# P_ytka.net
KiCad netlist of a schematic drawn in EAGLE
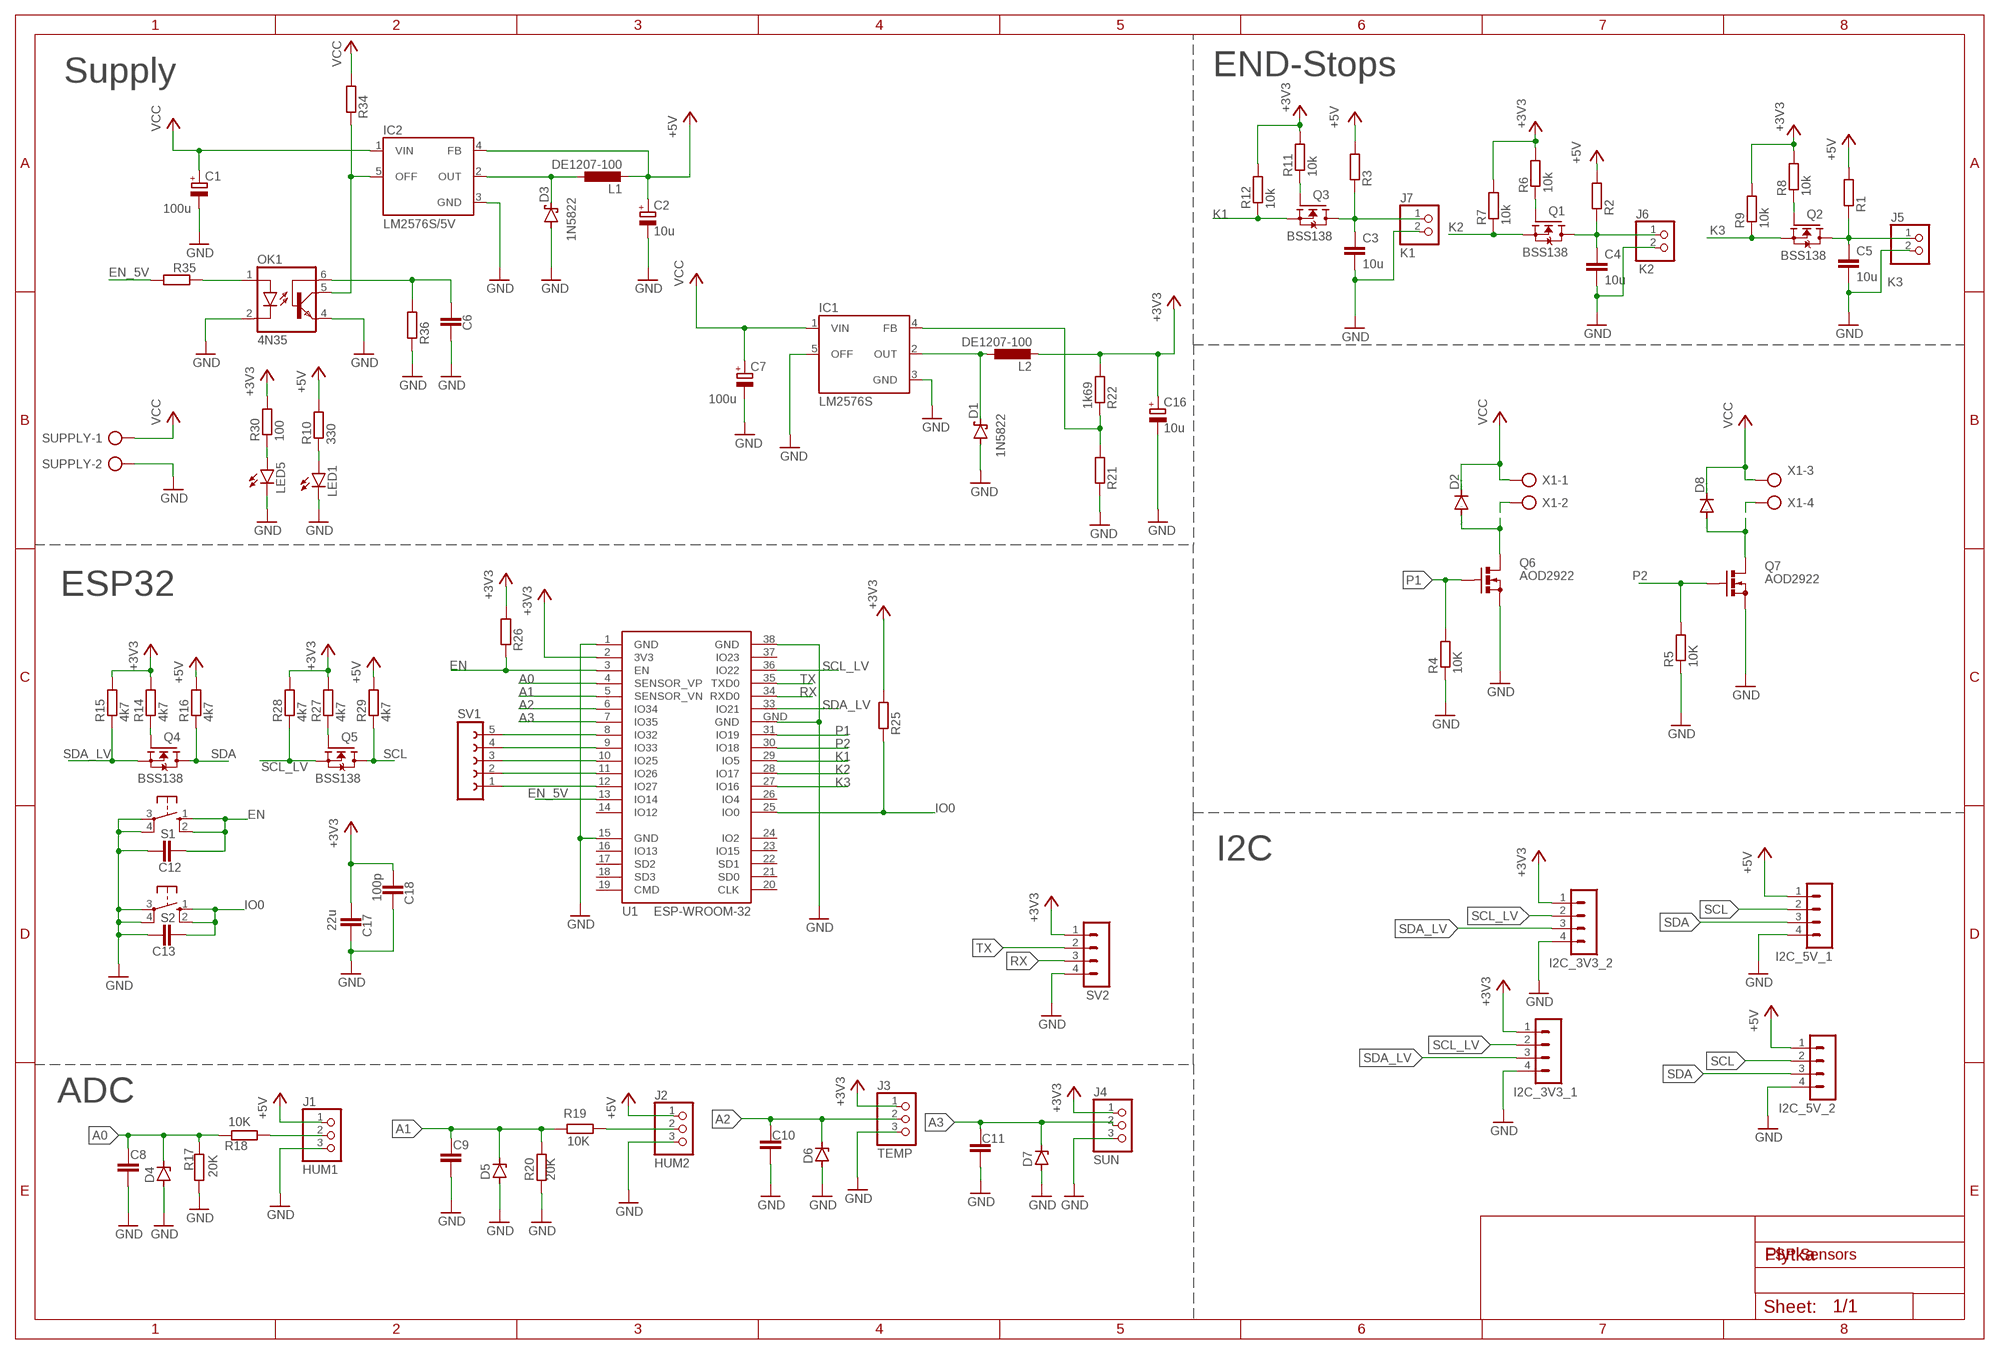
[diagram p0: schematic, sheet 1]

(export (version "E")
  (design (tool "Eeschema 10.0.6"))
  (components
    (comp (ref "C1")
      (value "100u")
      (footprint "eagle-import:E2,5-6")
      (libsource (lib "eagle-import") (part "CPOL-EUE2.5-6"))
    )
    (comp (ref "C2")
      (value "10u")
      (footprint "eagle-import:E3,5-8")
      (libsource (lib "eagle-import") (part "CPOL-EUE3.5-8"))
    )
    (comp (ref "C3")
      (value "10u")
      (footprint "eagle-import:C0805K")
      (libsource (lib "eagle-import") (part "C-EUC0805K"))
    )
    (comp (ref "C4")
      (value "10u")
      (footprint "eagle-import:C0805K")
      (libsource (lib "eagle-import") (part "C-EUC0805K"))
    )
    (comp (ref "C5")
      (value "10u")
      (footprint "eagle-import:C0805K")
      (libsource (lib "eagle-import") (part "C-EUC0805K"))
    )
    (comp (ref "C6")
      (value "C-EUC0805K")
      (footprint "eagle-import:C0805K")
      (libsource (lib "eagle-import") (part "C-EUC0805K"))
    )
    (comp (ref "C7")
      (value "100u")
      (footprint "eagle-import:E2,5-6")
      (libsource (lib "eagle-import") (part "CPOL-EUE2.5-6"))
    )
    (comp (ref "C8")
      (value "C-EUC0805K")
      (footprint "eagle-import:C0805K")
      (libsource (lib "eagle-import") (part "C-EUC0805K"))
    )
    (comp (ref "C9")
      (value "C-EUC0805K")
      (footprint "eagle-import:C0805K")
      (libsource (lib "eagle-import") (part "C-EUC0805K"))
    )
    (comp (ref "C10")
      (value "C-EUC0805K")
      (footprint "eagle-import:C0805K")
      (libsource (lib "eagle-import") (part "C-EUC0805K"))
    )
    (comp (ref "C11")
      (value "C-EUC0805K")
      (footprint "eagle-import:C0805K")
      (libsource (lib "eagle-import") (part "C-EUC0805K"))
    )
    (comp (ref "C12")
      (value "C-EUC0805K")
      (footprint "eagle-import:C0805K")
      (libsource (lib "eagle-import") (part "C-EUC0805K"))
    )
    (comp (ref "C13")
      (value "C-EUC0805K")
      (footprint "eagle-import:C0805K")
      (libsource (lib "eagle-import") (part "C-EUC0805K"))
    )
    (comp (ref "C16")
      (value "10u")
      (footprint "eagle-import:E3,5-8")
      (libsource (lib "eagle-import") (part "CPOL-EUE3.5-8"))
    )
    (comp (ref "C17")
      (value "22u")
      (footprint "eagle-import:C0805K")
      (libsource (lib "eagle-import") (part "C-EUC0805K"))
    )
    (comp (ref "C18")
      (value "100p")
      (footprint "eagle-import:C0805K")
      (libsource (lib "eagle-import") (part "C-EUC0805K"))
    )
    (comp (ref "D1")
      (value "1N5822")
      (footprint "eagle-import:C4111-15")
      (libsource (lib "eagle-import") (part "1N5908"))
    )
    (comp (ref "D2")
      (value "DIODE-DO214AC")
      (footprint "eagle-import:DO214AC")
      (libsource (lib "eagle-import") (part "DIODE-DO214AC"))
    )
    (comp (ref "D3")
      (value "1N5822")
      (footprint "eagle-import:C4111-15")
      (libsource (lib "eagle-import") (part "1N5908"))
    )
    (comp (ref "D4")
      (value "ZENER-DIODESOD80C")
      (footprint "eagle-import:SOD80C")
      (libsource (lib "eagle-import") (part "ZENER-DIODESOD80C"))
    )
    (comp (ref "D5")
      (value "ZENER-DIODESOD80C")
      (footprint "eagle-import:SOD80C")
      (libsource (lib "eagle-import") (part "ZENER-DIODESOD80C"))
    )
    (comp (ref "D6")
      (value "ZENER-DIODESOD80C")
      (footprint "eagle-import:SOD80C")
      (libsource (lib "eagle-import") (part "ZENER-DIODESOD80C"))
    )
    (comp (ref "D7")
      (value "ZENER-DIODESOD80C")
      (footprint "eagle-import:SOD80C")
      (libsource (lib "eagle-import") (part "ZENER-DIODESOD80C"))
    )
    (comp (ref "D8")
      (value "DIODE-DO214AC")
      (footprint "eagle-import:DO214AC")
      (libsource (lib "eagle-import") (part "DIODE-DO214AC"))
    )
    (comp (ref "I2C_3V3_1")
      (value "MA04-1")
      (footprint "eagle-import:MA04-1")
      (libsource (lib "eagle-import") (part "MA04-1"))
    )
    (comp (ref "I2C_3V3_2")
      (value "MA04-1")
      (footprint "eagle-import:MA04-1")
      (libsource (lib "eagle-import") (part "MA04-1"))
    )
    (comp (ref "I2C_5V_1")
      (value "MA04-1")
      (footprint "eagle-import:MA04-1")
      (libsource (lib "eagle-import") (part "MA04-1"))
    )
    (comp (ref "I2C_5V_2")
      (value "MA04-1")
      (footprint "eagle-import:MA04-1")
      (libsource (lib "eagle-import") (part "MA04-1"))
    )
    (comp (ref "IC1")
      (value "LM2576S")
      (footprint "eagle-import:TO263-5")
      (libsource (lib "eagle-import") (part "LM2576S"))
    )
    (comp (ref "IC2")
      (value "LM2576S/5V")
      (footprint "eagle-import:TO220-5")
      (libsource (lib "eagle-import") (part "LM2576T"))
    )
    (comp (ref "J1")
      (value "HUM1")
      (footprint "eagle-import:W_TYPE_2MM_3_N")
      (libsource (lib "eagle-import") (part "WT-2MM-3PINSTRAIGHT"))
    )
    (comp (ref "J2")
      (value "HUM2")
      (footprint "eagle-import:W_TYPE_2MM_3_N")
      (libsource (lib "eagle-import") (part "WT-2MM-3PINSTRAIGHT"))
    )
    (comp (ref "J3")
      (value "TEMP")
      (footprint "eagle-import:W_TYPE_2MM_3_N")
      (libsource (lib "eagle-import") (part "WT-2MM-3PINSTRAIGHT"))
    )
    (comp (ref "J4")
      (value "SUN")
      (footprint "eagle-import:W_TYPE_2MM_3_N")
      (libsource (lib "eagle-import") (part "WT-2MM-3PINSTRAIGHT"))
    )
    (comp (ref "J5")
      (value "K3")
      (footprint "eagle-import:W_TYPE_2MM_2_N")
      (libsource (lib "eagle-import") (part "WT-2MM-2PINSTRAIGHT"))
    )
    (comp (ref "J6")
      (value "K2")
      (footprint "eagle-import:W_TYPE_2MM_2_N")
      (libsource (lib "eagle-import") (part "WT-2MM-2PINSTRAIGHT"))
    )
    (comp (ref "J7")
      (value "K1")
      (footprint "eagle-import:W_TYPE_2MM_2_N")
      (libsource (lib "eagle-import") (part "WT-2MM-2PINSTRAIGHT"))
    )
    (comp (ref "L1")
      (value "DE1207-100")
      (footprint "eagle-import:DE1207")
      (libsource (lib "eagle-import") (part "DE1207-100"))
    )
    (comp (ref "L2")
      (value "DE1207-100")
      (footprint "eagle-import:DE1207")
      (libsource (lib "eagle-import") (part "DE1207-100"))
    )
    (comp (ref "LED1")
      (value "LEDSML0805")
      (footprint "eagle-import:SML0805")
      (libsource (lib "eagle-import") (part "LEDSML0805"))
    )
    (comp (ref "LED5")
      (value "LEDSML0805")
      (footprint "eagle-import:SML0805")
      (libsource (lib "eagle-import") (part "LEDSML0805"))
    )
    (comp (ref "OK1")
      (value "4N35")
      (footprint "eagle-import:DIL06")
      (fields (field (name "MF") "FAIRCHILD SEMICONDUCTOR"))
      (libsource (lib "eagle-import") (part "4N35"))
    )
    (comp (ref "Q1")
      (value "BSS138")
      (footprint "eagle-import:SOT23")
      (fields (field (name "MF") "Fairchild"))
      (libsource (lib "eagle-import") (part "BSS138"))
    )
    (comp (ref "Q2")
      (value "BSS138")
      (footprint "eagle-import:SOT23")
      (fields (field (name "MF") "Fairchild"))
      (libsource (lib "eagle-import") (part "BSS138"))
    )
    (comp (ref "Q3")
      (value "BSS138")
      (footprint "eagle-import:SOT23")
      (fields (field (name "MF") "Fairchild"))
      (libsource (lib "eagle-import") (part "BSS138"))
    )
    (comp (ref "Q4")
      (value "BSS138")
      (footprint "eagle-import:SOT23")
      (fields (field (name "MF") "Fairchild"))
      (libsource (lib "eagle-import") (part "BSS138"))
    )
    (comp (ref "Q5")
      (value "BSS138")
      (footprint "eagle-import:SOT23")
      (fields (field (name "MF") "Fairchild"))
      (libsource (lib "eagle-import") (part "BSS138"))
    )
    (comp (ref "Q6")
      (value "AOD2922")
      (footprint "eagle-import:TO252AA")
      (libsource (lib "eagle-import") (part "MOSFET_NIXTY8N65X2"))
    )
    (comp (ref "Q7")
      (value "AOD2922")
      (footprint "eagle-import:TO252AA")
      (libsource (lib "eagle-import") (part "MOSFET_NIXTY8N65X2"))
    )
    (comp (ref "R1")
      (value "R-EU_R0805")
      (footprint "eagle-import:R0805")
      (libsource (lib "eagle-import") (part "R-EU_R0805"))
    )
    (comp (ref "R2")
      (value "R-EU_R0805")
      (footprint "eagle-import:R0805")
      (libsource (lib "eagle-import") (part "R-EU_R0805"))
    )
    (comp (ref "R3")
      (value "R-EU_R0805")
      (footprint "eagle-import:R0805")
      (libsource (lib "eagle-import") (part "R-EU_R0805"))
    )
    (comp (ref "R4")
      (value "10K")
      (footprint "eagle-import:R0805")
      (libsource (lib "eagle-import") (part "R-EU_R0805"))
    )
    (comp (ref "R5")
      (value "10K")
      (footprint "eagle-import:R0805")
      (libsource (lib "eagle-import") (part "R-EU_R0805"))
    )
    (comp (ref "R6")
      (value "10k")
      (footprint "eagle-import:R0805")
      (libsource (lib "eagle-import") (part "R-EU_R0805"))
    )
    (comp (ref "R7")
      (value "10k")
      (footprint "eagle-import:R0805")
      (libsource (lib "eagle-import") (part "R-EU_R0805"))
    )
    (comp (ref "R8")
      (value "10k")
      (footprint "eagle-import:R0805")
      (libsource (lib "eagle-import") (part "R-EU_R0805"))
    )
    (comp (ref "R9")
      (value "10k")
      (footprint "eagle-import:R0805")
      (libsource (lib "eagle-import") (part "R-EU_R0805"))
    )
    (comp (ref "R10")
      (value "330")
      (footprint "eagle-import:R0805")
      (libsource (lib "eagle-import") (part "R-EU_R0805"))
    )
    (comp (ref "R11")
      (value "10k")
      (footprint "eagle-import:R0805")
      (libsource (lib "eagle-import") (part "R-EU_R0805"))
    )
    (comp (ref "R12")
      (value "10k")
      (footprint "eagle-import:R0805")
      (libsource (lib "eagle-import") (part "R-EU_R0805"))
    )
    (comp (ref "R14")
      (value "4k7")
      (footprint "eagle-import:R0805")
      (libsource (lib "eagle-import") (part "R-EU_R0805"))
    )
    (comp (ref "R15")
      (value "4k7")
      (footprint "eagle-import:R0805")
      (libsource (lib "eagle-import") (part "R-EU_R0805"))
    )
    (comp (ref "R16")
      (value "4k7")
      (footprint "eagle-import:R0805")
      (libsource (lib "eagle-import") (part "R-EU_R0805"))
    )
    (comp (ref "R17")
      (value "20K")
      (footprint "eagle-import:R0805")
      (libsource (lib "eagle-import") (part "R-EU_R0805"))
    )
    (comp (ref "R18")
      (value "10K")
      (footprint "eagle-import:R0805")
      (libsource (lib "eagle-import") (part "R-EU_R0805"))
    )
    (comp (ref "R19")
      (value "10K")
      (footprint "eagle-import:R0805")
      (libsource (lib "eagle-import") (part "R-EU_R0805"))
    )
    (comp (ref "R20")
      (value "20K")
      (footprint "eagle-import:R0805")
      (libsource (lib "eagle-import") (part "R-EU_R0805"))
    )
    (comp (ref "R21")
      (value "R-EU_R0805")
      (footprint "eagle-import:R0805")
      (libsource (lib "eagle-import") (part "R-EU_R0805"))
    )
    (comp (ref "R22")
      (value "1k69")
      (footprint "eagle-import:R0805")
      (libsource (lib "eagle-import") (part "R-EU_R0805"))
    )
    (comp (ref "R25")
      (value "R-EU_R0805")
      (footprint "eagle-import:R0805")
      (libsource (lib "eagle-import") (part "R-EU_R0805"))
    )
    (comp (ref "R26")
      (value "R-EU_R0805")
      (footprint "eagle-import:R0805")
      (libsource (lib "eagle-import") (part "R-EU_R0805"))
    )
    (comp (ref "R27")
      (value "4k7")
      (footprint "eagle-import:R0805")
      (libsource (lib "eagle-import") (part "R-EU_R0805"))
    )
    (comp (ref "R28")
      (value "4k7")
      (footprint "eagle-import:R0805")
      (libsource (lib "eagle-import") (part "R-EU_R0805"))
    )
    (comp (ref "R29")
      (value "4k7")
      (footprint "eagle-import:R0805")
      (libsource (lib "eagle-import") (part "R-EU_R0805"))
    )
    (comp (ref "R30")
      (value "100")
      (footprint "eagle-import:R0805")
      (libsource (lib "eagle-import") (part "R-EU_R0805"))
    )
    (comp (ref "R34")
      (value "R-EU_R0805")
      (footprint "eagle-import:R0805")
      (libsource (lib "eagle-import") (part "R-EU_R0805"))
    )
    (comp (ref "R35")
      (value "R-EU_R0805")
      (footprint "eagle-import:R0805")
      (libsource (lib "eagle-import") (part "R-EU_R0805"))
    )
    (comp (ref "R36")
      (value "R-EU_R0805")
      (footprint "eagle-import:R0805")
      (libsource (lib "eagle-import") (part "R-EU_R0805"))
    )
    (comp (ref "S1")
      (value "10-XX")
      (footprint "eagle-import:B3F-10XX")
      (fields (field (name "MPN") "B3F-1000"))
      (libsource (lib "eagle-import") (part "10-XX"))
    )
    (comp (ref "S2")
      (value "10-XX")
      (footprint "eagle-import:B3F-10XX")
      (fields (field (name "MPN") "B3F-1000"))
      (libsource (lib "eagle-import") (part "10-XX"))
    )
    (comp (ref "SUPPLY")
      (value "AK500/2-H")
      (footprint "eagle-import:AK500_2-H")
      (libsource (lib "eagle-import") (part "AK500/2-H"))
    )
    (comp (ref "SV1")
      (value "FE05-1")
      (footprint "eagle-import:FE05-1")
      (libsource (lib "eagle-import") (part "FE05-1"))
    )
    (comp (ref "SV2")
      (value "MA04-1")
      (footprint "eagle-import:MA04-1")
      (libsource (lib "eagle-import") (part "MA04-1"))
    )
    (comp (ref "U1")
      (value "ESP-WROOM-32")
      (footprint "eagle-import:ESP-WROOM-32")
      (libsource (lib "eagle-import") (part "ESP-WROOM-32"))
    )
    (comp (ref "X1")
      (value "+ P2")
      (footprint "eagle-import:AK500_4")
      (libsource (lib "eagle-import") (part "AK500/4"))
    )
  )
  (nets
    (net (code "1") (name "+3V3") (class "Default")
      (node (ref "C16") (pin "+") (pinfunction "+_+") (pintype "passive"))
      (node (ref "C17") (pin "2") (pinfunction "2_2") (pintype "passive"))
      (node (ref "C18") (pin "2") (pinfunction "2_2") (pintype "passive"))
      (node (ref "I2C_3V3_1") (pin "1") (pinfunction "1_1") (pintype "passive"))
      (node (ref "I2C_3V3_2") (pin "1") (pinfunction "1_1") (pintype "passive"))
      (node (ref "J3") (pin "1") (pinfunction "1_1") (pintype "passive"))
      (node (ref "J4") (pin "1") (pinfunction "1_1") (pintype "passive"))
      (node (ref "L2") (pin "2") (pinfunction "2_2") (pintype "passive"))
      (node (ref "R11") (pin "2") (pinfunction "2_2") (pintype "passive"))
      (node (ref "R12") (pin "2") (pinfunction "2_2") (pintype "passive"))
      (node (ref "R14") (pin "2") (pinfunction "2_2") (pintype "passive"))
      (node (ref "R15") (pin "2") (pinfunction "2_2") (pintype "passive"))
      (node (ref "R22") (pin "2") (pinfunction "2_2") (pintype "passive"))
      (node (ref "R25") (pin "2") (pinfunction "2_2") (pintype "passive"))
      (node (ref "R26") (pin "2") (pinfunction "2_2") (pintype "passive"))
      (node (ref "R27") (pin "2") (pinfunction "2_2") (pintype "passive"))
      (node (ref "R28") (pin "2") (pinfunction "2_2") (pintype "passive"))
      (node (ref "R30") (pin "2") (pinfunction "2_2") (pintype "passive"))
      (node (ref "R6") (pin "2") (pinfunction "2_2") (pintype "passive"))
      (node (ref "R7") (pin "2") (pinfunction "2_2") (pintype "passive"))
      (node (ref "R8") (pin "2") (pinfunction "2_2") (pintype "passive"))
      (node (ref "R9") (pin "2") (pinfunction "2_2") (pintype "passive"))
      (node (ref "SV2") (pin "1") (pinfunction "1_1") (pintype "passive"))
      (node (ref "U1") (pin "2") (pinfunction "3V3_2") (pintype "power_in"))
    )
    (net (code "2") (name "+5V") (class "Default")
      (node (ref "C2") (pin "+") (pinfunction "+_+") (pintype "passive"))
      (node (ref "I2C_5V_1") (pin "1") (pinfunction "1_1") (pintype "passive"))
      (node (ref "I2C_5V_2") (pin "1") (pinfunction "1_1") (pintype "passive"))
      (node (ref "IC2") (pin "4") (pinfunction "FB_4") (pintype "input"))
      (node (ref "J1") (pin "1") (pinfunction "1_1") (pintype "passive"))
      (node (ref "J2") (pin "1") (pinfunction "1_1") (pintype "passive"))
      (node (ref "L1") (pin "2") (pinfunction "2_2") (pintype "passive"))
      (node (ref "R1") (pin "2") (pinfunction "2_2") (pintype "passive"))
      (node (ref "R10") (pin "2") (pinfunction "2_2") (pintype "passive"))
      (node (ref "R16") (pin "2") (pinfunction "2_2") (pintype "passive"))
      (node (ref "R2") (pin "2") (pinfunction "2_2") (pintype "passive"))
      (node (ref "R29") (pin "2") (pinfunction "2_2") (pintype "passive"))
      (node (ref "R3") (pin "2") (pinfunction "2_2") (pintype "passive"))
    )
    (net (code "3") (name "/EN") (class "Default")
      (node (ref "C12") (pin "2") (pinfunction "2_2") (pintype "passive"))
      (node (ref "R26") (pin "1") (pinfunction "1_1") (pintype "passive"))
      (node (ref "S1") (pin "1") (pinfunction "S_1") (pintype "passive"))
      (node (ref "S1") (pin "2") (pinfunction "S1_2") (pintype "passive"))
      (node (ref "U1") (pin "3") (pinfunction "EN_3") (pintype "input"))
    )
    (net (code "4") (name "/EN_5V") (class "Default")
      (node (ref "R35") (pin "2") (pinfunction "2_2") (pintype "passive"))
      (node (ref "U1") (pin "13") (pinfunction "IO14_13") (pintype "bidirectional"))
    )
    (net (code "5") (name "/IO0") (class "Default")
      (node (ref "C13") (pin "2") (pinfunction "2_2") (pintype "passive"))
      (node (ref "R25") (pin "1") (pinfunction "1_1") (pintype "passive"))
      (node (ref "S2") (pin "1") (pinfunction "S_1") (pintype "passive"))
      (node (ref "S2") (pin "2") (pinfunction "S1_2") (pintype "passive"))
      (node (ref "U1") (pin "25") (pinfunction "IO0_25") (pintype "bidirectional"))
    )
    (net (code "6") (name "/K1") (class "Default")
      (node (ref "Q3") (pin "2") (pinfunction "S_2") (pintype "passive"))
      (node (ref "R12") (pin "1") (pinfunction "1_1") (pintype "passive"))
      (node (ref "U1") (pin "29") (pinfunction "IO5_29") (pintype "bidirectional"))
    )
    (net (code "7") (name "/K2") (class "Default")
      (node (ref "Q1") (pin "2") (pinfunction "S_2") (pintype "passive"))
      (node (ref "R7") (pin "1") (pinfunction "1_1") (pintype "passive"))
      (node (ref "U1") (pin "28") (pinfunction "IO17_28") (pintype "bidirectional"))
    )
    (net (code "8") (name "/K3") (class "Default")
      (node (ref "Q2") (pin "2") (pinfunction "S_2") (pintype "passive"))
      (node (ref "R9") (pin "1") (pinfunction "1_1") (pintype "passive"))
      (node (ref "U1") (pin "27") (pinfunction "IO16_27") (pintype "bidirectional"))
    )
    (net (code "9") (name "/P2") (class "Default")
      (node (ref "Q7") (pin "1") (pinfunction "G_1") (pintype "passive"))
      (node (ref "R5") (pin "2") (pinfunction "2_2") (pintype "passive"))
      (node (ref "U1") (pin "30") (pinfunction "IO18_30") (pintype "bidirectional"))
    )
    (net (code "10") (name "A0") (class "Default")
      (node (ref "C8") (pin "1") (pinfunction "1_1") (pintype "passive"))
      (node (ref "D4") (pin "C") (pinfunction "C_C") (pintype "passive"))
      (node (ref "R17") (pin "2") (pinfunction "2_2") (pintype "passive"))
      (node (ref "R18") (pin "2") (pinfunction "2_2") (pintype "passive"))
      (node (ref "U1") (pin "4") (pinfunction "SENSOR_VP_4") (pintype "bidirectional"))
    )
    (net (code "11") (name "A1") (class "Default")
      (node (ref "C9") (pin "1") (pinfunction "1_1") (pintype "passive"))
      (node (ref "D5") (pin "C") (pinfunction "C_C") (pintype "passive"))
      (node (ref "R19") (pin "2") (pinfunction "2_2") (pintype "passive"))
      (node (ref "R20") (pin "1") (pinfunction "1_1") (pintype "passive"))
      (node (ref "U1") (pin "5") (pinfunction "SENSOR_VN_5") (pintype "bidirectional"))
    )
    (net (code "12") (name "A2") (class "Default")
      (node (ref "C10") (pin "1") (pinfunction "1_1") (pintype "passive"))
      (node (ref "D6") (pin "C") (pinfunction "C_C") (pintype "passive"))
      (node (ref "J3") (pin "2") (pinfunction "2_2") (pintype "passive"))
      (node (ref "U1") (pin "6") (pinfunction "IO34_6") (pintype "bidirectional"))
    )
    (net (code "13") (name "A3") (class "Default")
      (node (ref "C11") (pin "1") (pinfunction "1_1") (pintype "passive"))
      (node (ref "D7") (pin "C") (pinfunction "C_C") (pintype "passive"))
      (node (ref "J4") (pin "2") (pinfunction "2_2") (pintype "passive"))
      (node (ref "U1") (pin "7") (pinfunction "IO35_7") (pintype "bidirectional"))
    )
    (net (code "14") (name "GND") (class "Default")
      (node (ref "C1") (pin "-") (pinfunction "-_-") (pintype "passive"))
      (node (ref "C10") (pin "2") (pinfunction "2_2") (pintype "passive"))
      (node (ref "C11") (pin "2") (pinfunction "2_2") (pintype "passive"))
      (node (ref "C12") (pin "1") (pinfunction "1_1") (pintype "passive"))
      (node (ref "C13") (pin "1") (pinfunction "1_1") (pintype "passive"))
      (node (ref "C16") (pin "-") (pinfunction "-_-") (pintype "passive"))
      (node (ref "C17") (pin "1") (pinfunction "1_1") (pintype "passive"))
      (node (ref "C18") (pin "1") (pinfunction "1_1") (pintype "passive"))
      (node (ref "C2") (pin "-") (pinfunction "-_-") (pintype "passive"))
      (node (ref "C3") (pin "2") (pinfunction "2_2") (pintype "passive"))
      (node (ref "C4") (pin "2") (pinfunction "2_2") (pintype "passive"))
      (node (ref "C5") (pin "2") (pinfunction "2_2") (pintype "passive"))
      (node (ref "C6") (pin "1") (pinfunction "1_1") (pintype "passive"))
      (node (ref "C7") (pin "-") (pinfunction "-_-") (pintype "passive"))
      (node (ref "C8") (pin "2") (pinfunction "2_2") (pintype "passive"))
      (node (ref "C9") (pin "2") (pinfunction "2_2") (pintype "passive"))
      (node (ref "D1") (pin "A") (pinfunction "A_A") (pintype "passive"))
      (node (ref "D3") (pin "A") (pinfunction "A_A") (pintype "passive"))
      (node (ref "D4") (pin "A") (pinfunction "A_A") (pintype "passive"))
      (node (ref "D5") (pin "A") (pinfunction "A_A") (pintype "passive"))
      (node (ref "D6") (pin "A") (pinfunction "A_A") (pintype "passive"))
      (node (ref "D7") (pin "A") (pinfunction "A_A") (pintype "passive"))
      (node (ref "I2C_3V3_1") (pin "4") (pinfunction "4_4") (pintype "passive"))
      (node (ref "I2C_3V3_2") (pin "4") (pinfunction "4_4") (pintype "passive"))
      (node (ref "I2C_5V_1") (pin "4") (pinfunction "4_4") (pintype "passive"))
      (node (ref "I2C_5V_2") (pin "4") (pinfunction "4_4") (pintype "passive"))
      (node (ref "IC1") (pin "3") (pinfunction "GND_3") (pintype "power_in"))
      (node (ref "IC1") (pin "5") (pinfunction "OFF_5") (pintype "input"))
      (node (ref "IC2") (pin "3") (pinfunction "GND_3") (pintype "power_in"))
      (node (ref "J1") (pin "3") (pinfunction "3_3") (pintype "passive"))
      (node (ref "J2") (pin "3") (pinfunction "3_3") (pintype "passive"))
      (node (ref "J3") (pin "3") (pinfunction "3_3") (pintype "passive"))
      (node (ref "J4") (pin "3") (pinfunction "3_3") (pintype "passive"))
      (node (ref "J5") (pin "2") (pinfunction "2_2") (pintype "passive"))
      (node (ref "J6") (pin "2") (pinfunction "2_2") (pintype "passive"))
      (node (ref "J7") (pin "2") (pinfunction "2_2") (pintype "passive"))
      (node (ref "LED1") (pin "C") (pinfunction "C_C") (pintype "passive"))
      (node (ref "LED5") (pin "C") (pinfunction "C_C") (pintype "passive"))
      (node (ref "OK1") (pin "2") (pinfunction "C_2") (pintype "passive"))
      (node (ref "OK1") (pin "4") (pinfunction "EMI_4") (pintype "passive"))
      (node (ref "Q6") (pin "2") (pinfunction "S_2") (pintype "passive"))
      (node (ref "Q7") (pin "2") (pinfunction "S_2") (pintype "passive"))
      (node (ref "R17") (pin "1") (pinfunction "1_1") (pintype "passive"))
      (node (ref "R20") (pin "2") (pinfunction "2_2") (pintype "passive"))
      (node (ref "R21") (pin "1") (pinfunction "1_1") (pintype "passive"))
      (node (ref "R36") (pin "1") (pinfunction "1_1") (pintype "passive"))
      (node (ref "R4") (pin "1") (pinfunction "1_1") (pintype "passive"))
      (node (ref "R5") (pin "1") (pinfunction "1_1") (pintype "passive"))
      (node (ref "S1") (pin "3") (pinfunction "P_3") (pintype "passive"))
      (node (ref "S1") (pin "4") (pinfunction "P1_4") (pintype "passive"))
      (node (ref "S2") (pin "3") (pinfunction "P_3") (pintype "passive"))
      (node (ref "S2") (pin "4") (pinfunction "P1_4") (pintype "passive"))
      (node (ref "SUPPLY") (pin "2") (pinfunction "KL_2") (pintype "passive"))
      (node (ref "SV2") (pin "4") (pinfunction "4_4") (pintype "passive"))
      (node (ref "U1") (pin "1") (pinfunction "GND_1") (pintype "power_in"))
      (node (ref "U1") (pin "15") (pinfunction "GND_15") (pintype "power_in"))
      (node (ref "U1") (pin "38") (pinfunction "GND_38") (pintype "power_in"))
      (node (ref "U1") (pin "GND") (pinfunction "GND_GND") (pintype "power_in"))
    )
    (net (code "15") (name "Net-(IC1-FB)") (class "Default")
      (node (ref "IC1") (pin "4") (pinfunction "FB_4") (pintype "input"))
      (node (ref "R21") (pin "2") (pinfunction "2_2") (pintype "passive"))
      (node (ref "R22") (pin "1") (pinfunction "1_1") (pintype "passive"))
    )
    (net (code "16") (name "Net-(IC1-OUT)") (class "Default")
      (node (ref "D1") (pin "C") (pinfunction "C_C") (pintype "passive"))
      (node (ref "IC1") (pin "2") (pinfunction "OUT_2") (pintype "output"))
      (node (ref "L2") (pin "1") (pinfunction "1_1") (pintype "passive"))
    )
    (net (code "17") (name "Net-(IC2-OFF)") (class "Default")
      (node (ref "IC2") (pin "5") (pinfunction "OFF_5") (pintype "input"))
      (node (ref "OK1") (pin "5") (pinfunction "COL_5") (pintype "passive"))
      (node (ref "R34") (pin "1") (pinfunction "1_1") (pintype "passive"))
    )
    (net (code "18") (name "Net-(IC2-OUT)") (class "Default")
      (node (ref "D3") (pin "C") (pinfunction "C_C") (pintype "passive"))
      (node (ref "IC2") (pin "2") (pinfunction "OUT_2") (pintype "output"))
      (node (ref "L1") (pin "1") (pinfunction "1_1") (pintype "passive"))
    )
    (net (code "19") (name "Net-(J1-Pad2)") (class "Default")
      (node (ref "J1") (pin "2") (pinfunction "2_2") (pintype "passive"))
      (node (ref "R18") (pin "1") (pinfunction "1_1") (pintype "passive"))
    )
    (net (code "20") (name "Net-(J2-Pad2)") (class "Default")
      (node (ref "J2") (pin "2") (pinfunction "2_2") (pintype "passive"))
      (node (ref "R19") (pin "1") (pinfunction "1_1") (pintype "passive"))
    )
    (net (code "21") (name "Net-(LED1-PadA)") (class "Default")
      (node (ref "LED1") (pin "A") (pinfunction "A_A") (pintype "passive"))
      (node (ref "R10") (pin "1") (pinfunction "1_1") (pintype "passive"))
    )
    (net (code "22") (name "Net-(LED5-PadA)") (class "Default")
      (node (ref "LED5") (pin "A") (pinfunction "A_A") (pintype "passive"))
      (node (ref "R30") (pin "1") (pinfunction "1_1") (pintype "passive"))
    )
    (net (code "23") (name "Net-(OK1-A)") (class "Default")
      (node (ref "OK1") (pin "1") (pinfunction "A_1") (pintype "passive"))
      (node (ref "R35") (pin "1") (pinfunction "1_1") (pintype "passive"))
    )
    (net (code "24") (name "Net-(OK1-BAS)") (class "Default")
      (node (ref "C6") (pin "2") (pinfunction "2_2") (pintype "passive"))
      (node (ref "OK1") (pin "6") (pinfunction "BAS_6") (pintype "passive"))
      (node (ref "R36") (pin "2") (pinfunction "2_2") (pintype "passive"))
    )
    (net (code "25") (name "Net-(Q1-D)") (class "Default")
      (node (ref "C4") (pin "1") (pinfunction "1_1") (pintype "passive"))
      (node (ref "J6") (pin "1") (pinfunction "1_1") (pintype "passive"))
      (node (ref "Q1") (pin "3") (pinfunction "D_3") (pintype "passive"))
      (node (ref "R2") (pin "1") (pinfunction "1_1") (pintype "passive"))
    )
    (net (code "26") (name "Net-(Q1-G)") (class "Default")
      (node (ref "Q1") (pin "1") (pinfunction "G_1") (pintype "passive"))
      (node (ref "R6") (pin "1") (pinfunction "1_1") (pintype "passive"))
    )
    (net (code "27") (name "Net-(Q2-D)") (class "Default")
      (node (ref "C5") (pin "1") (pinfunction "1_1") (pintype "passive"))
      (node (ref "J5") (pin "1") (pinfunction "1_1") (pintype "passive"))
      (node (ref "Q2") (pin "3") (pinfunction "D_3") (pintype "passive"))
      (node (ref "R1") (pin "1") (pinfunction "1_1") (pintype "passive"))
    )
    (net (code "28") (name "Net-(Q2-G)") (class "Default")
      (node (ref "Q2") (pin "1") (pinfunction "G_1") (pintype "passive"))
      (node (ref "R8") (pin "1") (pinfunction "1_1") (pintype "passive"))
    )
    (net (code "29") (name "Net-(Q3-D)") (class "Default")
      (node (ref "C3") (pin "1") (pinfunction "1_1") (pintype "passive"))
      (node (ref "J7") (pin "1") (pinfunction "1_1") (pintype "passive"))
      (node (ref "Q3") (pin "3") (pinfunction "D_3") (pintype "passive"))
      (node (ref "R3") (pin "1") (pinfunction "1_1") (pintype "passive"))
    )
    (net (code "30") (name "Net-(Q3-G)") (class "Default")
      (node (ref "Q3") (pin "1") (pinfunction "G_1") (pintype "passive"))
      (node (ref "R11") (pin "1") (pinfunction "1_1") (pintype "passive"))
    )
    (net (code "31") (name "Net-(Q4-G)") (class "Default")
      (node (ref "Q4") (pin "1") (pinfunction "G_1") (pintype "passive"))
      (node (ref "R14") (pin "1") (pinfunction "1_1") (pintype "passive"))
    )
    (net (code "32") (name "Net-(Q5-G)") (class "Default")
      (node (ref "Q5") (pin "1") (pinfunction "G_1") (pintype "passive"))
      (node (ref "R27") (pin "1") (pinfunction "1_1") (pintype "passive"))
    )
    (net (code "33") (name "Net-(Q6-D)") (class "Default")
      (node (ref "D2") (pin "A") (pinfunction "A_A") (pintype "passive"))
      (node (ref "Q6") (pin "3") (pinfunction "D_3") (pintype "passive"))
      (node (ref "X1") (pin "2") (pinfunction "KL_2") (pintype "passive"))
    )
    (net (code "34") (name "Net-(Q7-D)") (class "Default")
      (node (ref "D8") (pin "A") (pinfunction "A_A") (pintype "passive"))
      (node (ref "Q7") (pin "3") (pinfunction "D_3") (pintype "passive"))
      (node (ref "X1") (pin "4") (pinfunction "KL_4") (pintype "passive"))
    )
    (net (code "35") (name "Net-(U1-IO25)") (class "Default")
      (node (ref "SV1") (pin "3") (pinfunction "3_3") (pintype "passive"))
      (node (ref "U1") (pin "10") (pinfunction "IO25_10") (pintype "bidirectional"))
    )
    (net (code "36") (name "Net-(U1-IO26)") (class "Default")
      (node (ref "SV1") (pin "2") (pinfunction "2_2") (pintype "passive"))
      (node (ref "U1") (pin "11") (pinfunction "IO26_11") (pintype "bidirectional"))
    )
    (net (code "37") (name "Net-(U1-IO27)") (class "Default")
      (node (ref "SV1") (pin "1") (pinfunction "1_1") (pintype "passive"))
      (node (ref "U1") (pin "12") (pinfunction "IO27_12") (pintype "bidirectional"))
    )
    (net (code "38") (name "Net-(U1-IO32)") (class "Default")
      (node (ref "SV1") (pin "5") (pinfunction "5_5") (pintype "passive"))
      (node (ref "U1") (pin "8") (pinfunction "IO32_8") (pintype "bidirectional"))
    )
    (net (code "39") (name "Net-(U1-IO33)") (class "Default")
      (node (ref "SV1") (pin "4") (pinfunction "4_4") (pintype "passive"))
      (node (ref "U1") (pin "9") (pinfunction "IO33_9") (pintype "bidirectional"))
    )
    (net (code "40") (name "P1") (class "Default")
      (node (ref "Q6") (pin "1") (pinfunction "G_1") (pintype "passive"))
      (node (ref "R4") (pin "2") (pinfunction "2_2") (pintype "passive"))
      (node (ref "U1") (pin "31") (pinfunction "IO19_31") (pintype "bidirectional"))
    )
    (net (code "41") (name "RX") (class "Default")
      (node (ref "SV2") (pin "3") (pinfunction "3_3") (pintype "passive"))
      (node (ref "U1") (pin "34") (pinfunction "RXD0_34") (pintype "bidirectional"))
    )
    (net (code "42") (name "SCL") (class "Default")
      (node (ref "I2C_5V_1") (pin "2") (pinfunction "2_2") (pintype "passive"))
      (node (ref "I2C_5V_2") (pin "2") (pinfunction "2_2") (pintype "passive"))
      (node (ref "Q5") (pin "3") (pinfunction "D_3") (pintype "passive"))
      (node (ref "R29") (pin "1") (pinfunction "1_1") (pintype "passive"))
    )
    (net (code "43") (name "SCL_LV") (class "Default")
      (node (ref "I2C_3V3_1") (pin "2") (pinfunction "2_2") (pintype "passive"))
      (node (ref "I2C_3V3_2") (pin "2") (pinfunction "2_2") (pintype "passive"))
      (node (ref "Q5") (pin "2") (pinfunction "S_2") (pintype "passive"))
      (node (ref "R28") (pin "1") (pinfunction "1_1") (pintype "passive"))
      (node (ref "U1") (pin "36") (pinfunction "IO22_36") (pintype "bidirectional"))
    )
    (net (code "44") (name "SDA") (class "Default")
      (node (ref "I2C_5V_1") (pin "3") (pinfunction "3_3") (pintype "passive"))
      (node (ref "I2C_5V_2") (pin "3") (pinfunction "3_3") (pintype "passive"))
      (node (ref "Q4") (pin "3") (pinfunction "D_3") (pintype "passive"))
      (node (ref "R16") (pin "1") (pinfunction "1_1") (pintype "passive"))
    )
    (net (code "45") (name "SDA_LV") (class "Default")
      (node (ref "I2C_3V3_1") (pin "3") (pinfunction "3_3") (pintype "passive"))
      (node (ref "I2C_3V3_2") (pin "3") (pinfunction "3_3") (pintype "passive"))
      (node (ref "Q4") (pin "2") (pinfunction "S_2") (pintype "passive"))
      (node (ref "R15") (pin "1") (pinfunction "1_1") (pintype "passive"))
      (node (ref "U1") (pin "33") (pinfunction "IO21_33") (pintype "bidirectional"))
    )
    (net (code "46") (name "TX") (class "Default")
      (node (ref "SV2") (pin "2") (pinfunction "2_2") (pintype "passive"))
      (node (ref "U1") (pin "35") (pinfunction "TXD0_35") (pintype "bidirectional"))
    )
    (net (code "47") (name "VCC") (class "Default")
      (node (ref "C1") (pin "+") (pinfunction "+_+") (pintype "passive"))
      (node (ref "C7") (pin "+") (pinfunction "+_+") (pintype "passive"))
      (node (ref "D2") (pin "C") (pinfunction "C_C") (pintype "passive"))
      (node (ref "D8") (pin "C") (pinfunction "C_C") (pintype "passive"))
      (node (ref "IC1") (pin "1") (pinfunction "VIN_1") (pintype "power_in"))
      (node (ref "IC2") (pin "1") (pinfunction "VIN_1") (pintype "power_in"))
      (node (ref "R34") (pin "2") (pinfunction "2_2") (pintype "passive"))
      (node (ref "SUPPLY") (pin "1") (pinfunction "KL_1") (pintype "passive"))
      (node (ref "X1") (pin "1") (pinfunction "KL_1") (pintype "passive"))
      (node (ref "X1") (pin "3") (pinfunction "KL_3") (pintype "passive"))
    )
    (net (code "48") (name "unconnected-(U1-CLK-Pad20)") (class "Default")
      (node (ref "U1") (pin "20") (pinfunction "CLK_20") (pintype "bidirectional"))
    )
    (net (code "49") (name "unconnected-(U1-CMD-Pad19)") (class "Default")
      (node (ref "U1") (pin "19") (pinfunction "CMD_19") (pintype "bidirectional"))
    )
    (net (code "50") (name "unconnected-(U1-IO2-Pad24)") (class "Default")
      (node (ref "U1") (pin "24") (pinfunction "IO2_24") (pintype "bidirectional"))
    )
    (net (code "51") (name "unconnected-(U1-IO4-Pad26)") (class "Default")
      (node (ref "U1") (pin "26") (pinfunction "IO4_26") (pintype "bidirectional"))
    )
    (net (code "52") (name "unconnected-(U1-IO12-Pad14)") (class "Default")
      (node (ref "U1") (pin "14") (pinfunction "IO12_14") (pintype "bidirectional"))
    )
    (net (code "53") (name "unconnected-(U1-IO13-Pad16)") (class "Default")
      (node (ref "U1") (pin "16") (pinfunction "IO13_16") (pintype "bidirectional"))
    )
    (net (code "54") (name "unconnected-(U1-IO15-Pad23)") (class "Default")
      (node (ref "U1") (pin "23") (pinfunction "IO15_23") (pintype "bidirectional"))
    )
    (net (code "55") (name "unconnected-(U1-IO23-Pad37)") (class "Default")
      (node (ref "U1") (pin "37") (pinfunction "IO23_37") (pintype "bidirectional"))
    )
    (net (code "56") (name "unconnected-(U1-SD0-Pad21)") (class "Default")
      (node (ref "U1") (pin "21") (pinfunction "SD0_21") (pintype "bidirectional"))
    )
    (net (code "57") (name "unconnected-(U1-SD1-Pad22)") (class "Default")
      (node (ref "U1") (pin "22") (pinfunction "SD1_22") (pintype "bidirectional"))
    )
    (net (code "58") (name "unconnected-(U1-SD2-Pad17)") (class "Default")
      (node (ref "U1") (pin "17") (pinfunction "SD2_17") (pintype "bidirectional"))
    )
    (net (code "59") (name "unconnected-(U1-SD3-Pad18)") (class "Default")
      (node (ref "U1") (pin "18") (pinfunction "SD3_18") (pintype "bidirectional"))
    )
  )
)
